# RF_test_board.net
KiCad netlist of a schematic drawn in EAGLE
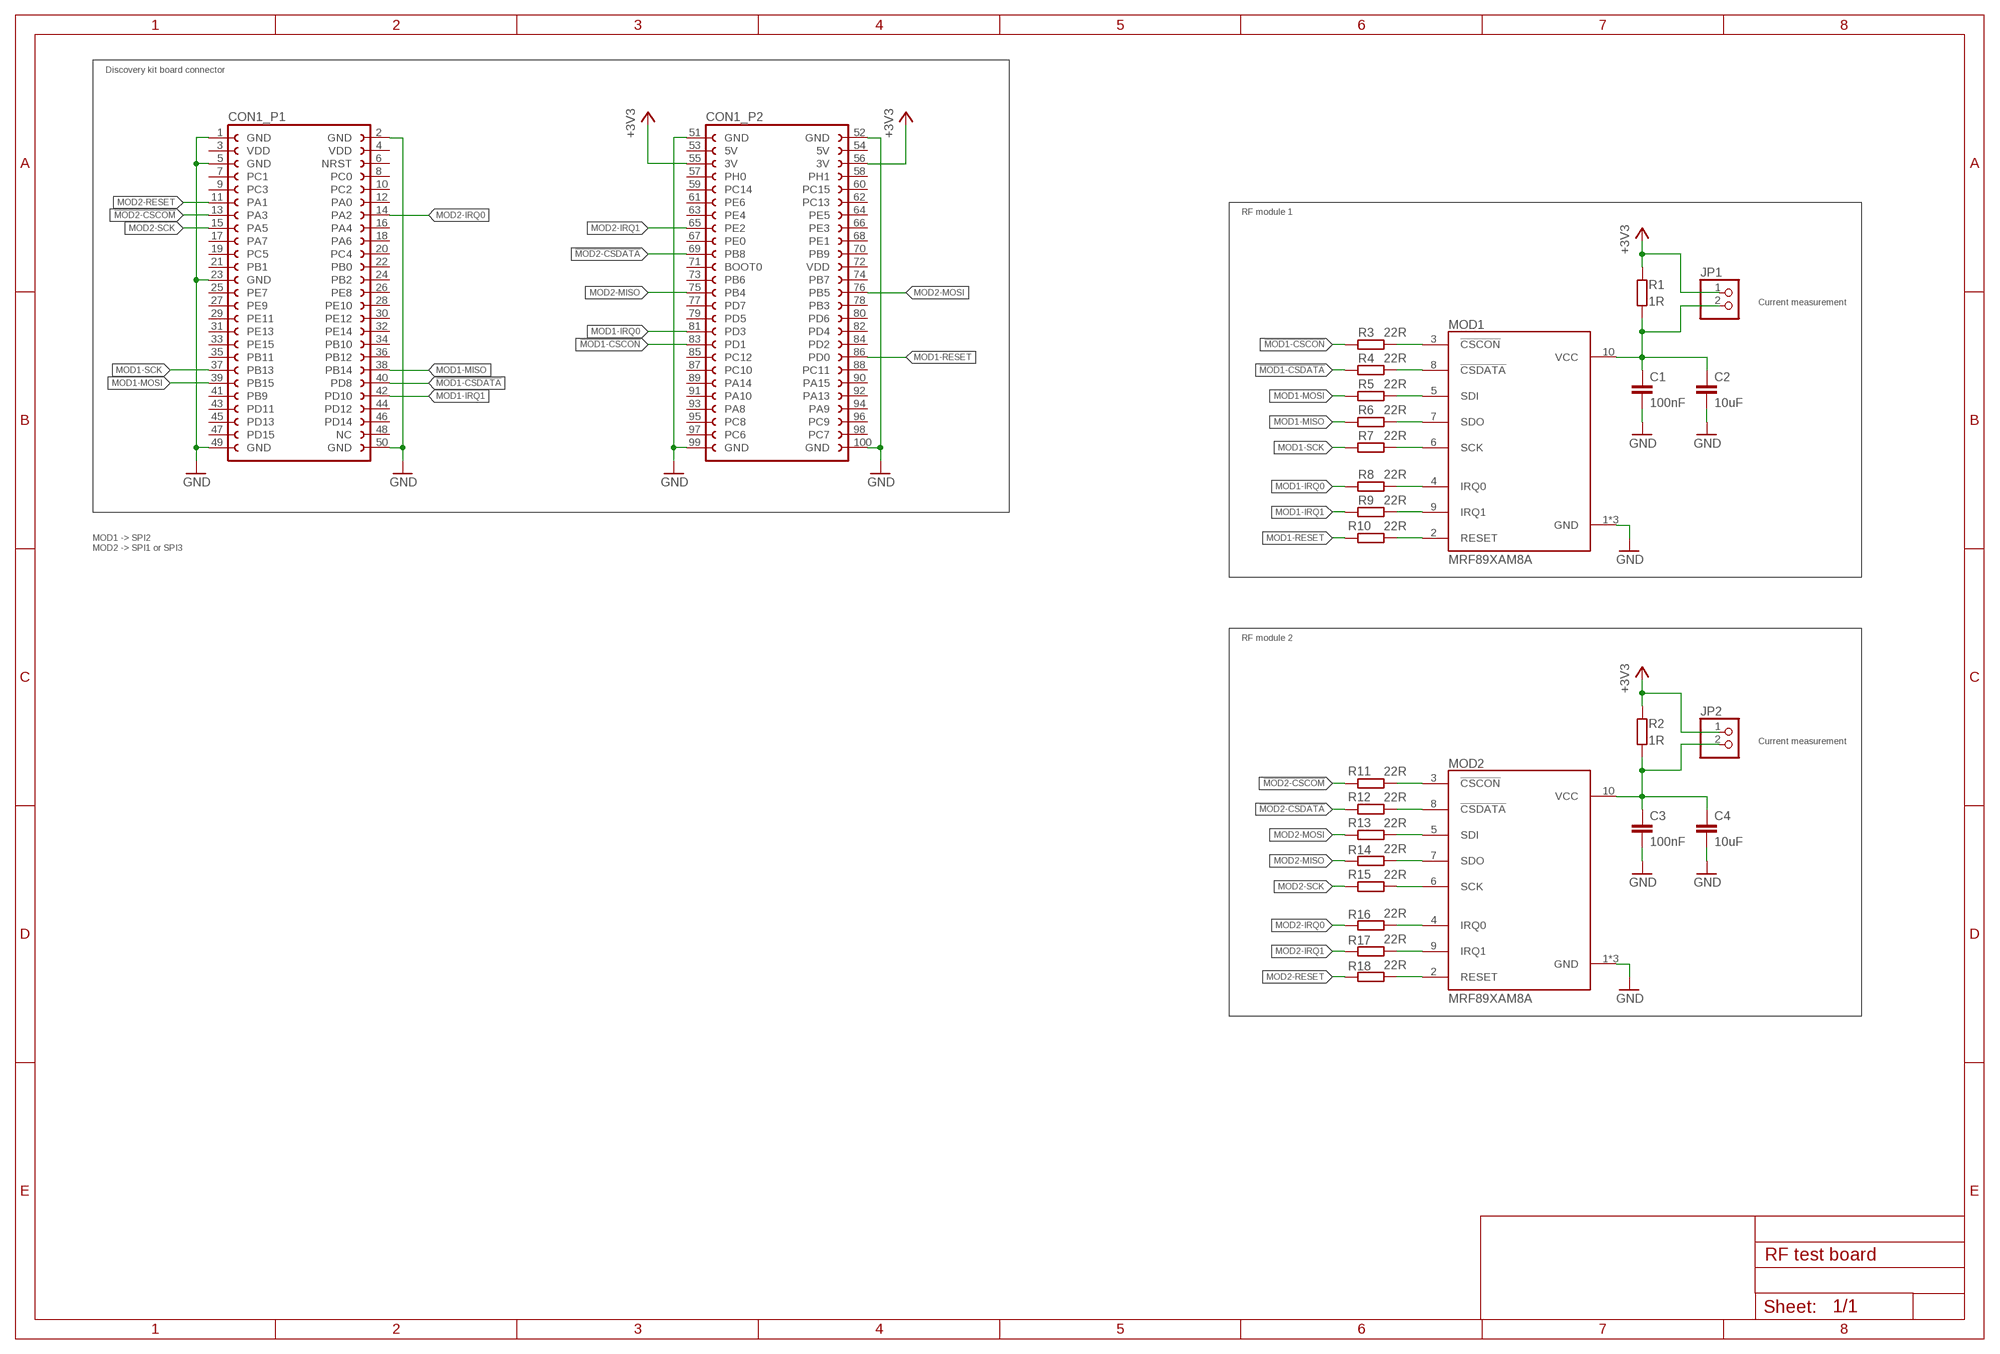
[diagram p0: schematic, sheet 1]

(export (version "E")
  (design (tool "Eeschema 10.0.6"))
  (components
    (comp (ref "C1")
      (value "100nF")
      (footprint "eagle-import:C0603K")
      (libsource (lib "eagle-import") (part "C-EUC0603K"))
    )
    (comp (ref "C2")
      (value "10uF")
      (footprint "eagle-import:C1206K")
      (libsource (lib "eagle-import") (part "C-EUC1206K"))
    )
    (comp (ref "C3")
      (value "100nF")
      (footprint "eagle-import:C0603K")
      (libsource (lib "eagle-import") (part "C-EUC0603K"))
    )
    (comp (ref "C4")
      (value "10uF")
      (footprint "eagle-import:C1206K")
      (libsource (lib "eagle-import") (part "C-EUC1206K"))
    )
    (comp (ref "CON1")
      (value "STM32F4DISCOVERY-CONNECTOR")
      (footprint "eagle-import:STM32F4DISCOVERY_CONNECTOR")
      (libsource (lib "eagle-import") (part "STM32F4DISCOVERY-CONNECTOR"))
    )
    (comp (ref "JP1")
      (value "PINHD-1X2")
      (footprint "eagle-import:1X02")
      (libsource (lib "eagle-import") (part "PINHD-1X2"))
    )
    (comp (ref "JP2")
      (value "PINHD-1X2")
      (footprint "eagle-import:1X02")
      (libsource (lib "eagle-import") (part "PINHD-1X2"))
    )
    (comp (ref "MOD1")
      (value "MRF89XAM8A")
      (footprint "eagle-import:MRF89XAM8A")
      (libsource (lib "eagle-import") (part "MRF89XAM8A"))
    )
    (comp (ref "MOD2")
      (value "MRF89XAM8A")
      (footprint "eagle-import:MRF89XAM8A")
      (libsource (lib "eagle-import") (part "MRF89XAM8A"))
    )
    (comp (ref "R1")
      (value "1R")
      (footprint "eagle-import:R0603")
      (libsource (lib "eagle-import") (part "R-EU_R0603"))
    )
    (comp (ref "R2")
      (value "1R")
      (footprint "eagle-import:R0603")
      (libsource (lib "eagle-import") (part "R-EU_R0603"))
    )
    (comp (ref "R3")
      (value "22R")
      (footprint "eagle-import:R0603")
      (libsource (lib "eagle-import") (part "R-EU_R0603"))
    )
    (comp (ref "R4")
      (value "22R")
      (footprint "eagle-import:R0603")
      (libsource (lib "eagle-import") (part "R-EU_R0603"))
    )
    (comp (ref "R5")
      (value "22R")
      (footprint "eagle-import:R0603")
      (libsource (lib "eagle-import") (part "R-EU_R0603"))
    )
    (comp (ref "R6")
      (value "22R")
      (footprint "eagle-import:R0603")
      (libsource (lib "eagle-import") (part "R-EU_R0603"))
    )
    (comp (ref "R7")
      (value "22R")
      (footprint "eagle-import:R0603")
      (libsource (lib "eagle-import") (part "R-EU_R0603"))
    )
    (comp (ref "R8")
      (value "22R")
      (footprint "eagle-import:R0603")
      (libsource (lib "eagle-import") (part "R-EU_R0603"))
    )
    (comp (ref "R9")
      (value "22R")
      (footprint "eagle-import:R0603")
      (libsource (lib "eagle-import") (part "R-EU_R0603"))
    )
    (comp (ref "R10")
      (value "22R")
      (footprint "eagle-import:R0603")
      (libsource (lib "eagle-import") (part "R-EU_R0603"))
    )
    (comp (ref "R11")
      (value "22R")
      (footprint "eagle-import:R0603")
      (libsource (lib "eagle-import") (part "R-EU_R0603"))
    )
    (comp (ref "R12")
      (value "22R")
      (footprint "eagle-import:R0603")
      (libsource (lib "eagle-import") (part "R-EU_R0603"))
    )
    (comp (ref "R13")
      (value "22R")
      (footprint "eagle-import:R0603")
      (libsource (lib "eagle-import") (part "R-EU_R0603"))
    )
    (comp (ref "R14")
      (value "22R")
      (footprint "eagle-import:R0603")
      (libsource (lib "eagle-import") (part "R-EU_R0603"))
    )
    (comp (ref "R15")
      (value "22R")
      (footprint "eagle-import:R0603")
      (libsource (lib "eagle-import") (part "R-EU_R0603"))
    )
    (comp (ref "R16")
      (value "22R")
      (footprint "eagle-import:R0603")
      (libsource (lib "eagle-import") (part "R-EU_R0603"))
    )
    (comp (ref "R17")
      (value "22R")
      (footprint "eagle-import:R0603")
      (libsource (lib "eagle-import") (part "R-EU_R0603"))
    )
    (comp (ref "R18")
      (value "22R")
      (footprint "eagle-import:R0603")
      (libsource (lib "eagle-import") (part "R-EU_R0603"))
    )
  )
  (nets
    (net (code "1") (name "+3V3") (class "Default")
      (node (ref "CON1") (pin "55") (pinfunction "3V_55") (pintype "passive"))
      (node (ref "CON1") (pin "56") (pinfunction "3V_56") (pintype "passive"))
      (node (ref "JP1") (pin "1") (pinfunction "1_1") (pintype "passive"))
      (node (ref "JP2") (pin "1") (pinfunction "1_1") (pintype "passive"))
      (node (ref "R1") (pin "2") (pinfunction "2_2") (pintype "passive"))
      (node (ref "R2") (pin "2") (pinfunction "2_2") (pintype "passive"))
    )
    (net (code "2") (name "/~{MOD1-CSCON}") (class "Default")
      (node (ref "CON1") (pin "83") (pinfunction "PD1_83") (pintype "passive"))
      (node (ref "R3") (pin "2") (pinfunction "2_2") (pintype "passive"))
    )
    (net (code "3") (name "/~{MOD1-CSDATA}") (class "Default")
      (node (ref "CON1") (pin "40") (pinfunction "PD8_40") (pintype "passive"))
      (node (ref "R4") (pin "2") (pinfunction "2_2") (pintype "passive"))
    )
    (net (code "4") (name "/~{MOD2-CSCOM}") (class "Default")
      (node (ref "CON1") (pin "13") (pinfunction "PA3_13") (pintype "passive"))
      (node (ref "R11") (pin "2") (pinfunction "2_2") (pintype "passive"))
    )
    (net (code "5") (name "/~{MOD2-CSDATA}") (class "Default")
      (node (ref "CON1") (pin "69") (pinfunction "PB8_69") (pintype "passive"))
      (node (ref "R12") (pin "2") (pinfunction "2_2") (pintype "passive"))
    )
    (net (code "6") (name "GND") (class "Default")
      (node (ref "C1") (pin "2") (pinfunction "2_2") (pintype "passive"))
      (node (ref "C2") (pin "2") (pinfunction "2_2") (pintype "passive"))
      (node (ref "C3") (pin "2") (pinfunction "2_2") (pintype "passive"))
      (node (ref "C4") (pin "2") (pinfunction "2_2") (pintype "passive"))
      (node (ref "CON1") (pin "1") (pinfunction "GND_1") (pintype "passive"))
      (node (ref "CON1") (pin "100") (pinfunction "GND_100") (pintype "passive"))
      (node (ref "CON1") (pin "2") (pinfunction "GND_2") (pintype "passive"))
      (node (ref "CON1") (pin "23") (pinfunction "GND_23") (pintype "passive"))
      (node (ref "CON1") (pin "49") (pinfunction "GND_49") (pintype "passive"))
      (node (ref "CON1") (pin "5") (pinfunction "GND_5") (pintype "passive"))
      (node (ref "CON1") (pin "50") (pinfunction "GND_50") (pintype "passive"))
      (node (ref "CON1") (pin "51") (pinfunction "GND_51") (pintype "passive"))
      (node (ref "CON1") (pin "52") (pinfunction "GND_52") (pintype "passive"))
      (node (ref "CON1") (pin "99") (pinfunction "GND_99") (pintype "passive"))
      (node (ref "MOD1") (pin "1") (pinfunction "GND_1") (pintype "bidirectional"))
      (node (ref "MOD1") (pin "11") (pinfunction "GND_11") (pintype "bidirectional"))
      (node (ref "MOD1") (pin "12") (pinfunction "GND_12") (pintype "bidirectional"))
      (node (ref "MOD2") (pin "1") (pinfunction "GND_1") (pintype "bidirectional"))
      (node (ref "MOD2") (pin "11") (pinfunction "GND_11") (pintype "bidirectional"))
      (node (ref "MOD2") (pin "12") (pinfunction "GND_12") (pintype "bidirectional"))
    )
    (net (code "7") (name "MOD1-IRQ0") (class "Default")
      (node (ref "CON1") (pin "81") (pinfunction "PD3_81") (pintype "passive"))
      (node (ref "R8") (pin "2") (pinfunction "2_2") (pintype "passive"))
    )
    (net (code "8") (name "MOD1-IRQ1") (class "Default")
      (node (ref "CON1") (pin "42") (pinfunction "PD10_42") (pintype "passive"))
      (node (ref "R9") (pin "2") (pinfunction "2_2") (pintype "passive"))
    )
    (net (code "9") (name "MOD1-MISO") (class "Default")
      (node (ref "CON1") (pin "38") (pinfunction "PB14_38") (pintype "passive"))
      (node (ref "R6") (pin "2") (pinfunction "2_2") (pintype "passive"))
    )
    (net (code "10") (name "MOD1-MOSI") (class "Default")
      (node (ref "CON1") (pin "39") (pinfunction "PB15_39") (pintype "passive"))
      (node (ref "R5") (pin "2") (pinfunction "2_2") (pintype "passive"))
    )
    (net (code "11") (name "MOD1-RESET") (class "Default")
      (node (ref "CON1") (pin "86") (pinfunction "PD0_86") (pintype "passive"))
      (node (ref "R10") (pin "2") (pinfunction "2_2") (pintype "passive"))
    )
    (net (code "12") (name "MOD1-SCK") (class "Default")
      (node (ref "CON1") (pin "37") (pinfunction "PB13_37") (pintype "passive"))
      (node (ref "R7") (pin "2") (pinfunction "2_2") (pintype "passive"))
    )
    (net (code "13") (name "MOD2-IRQ0") (class "Default")
      (node (ref "CON1") (pin "14") (pinfunction "PA2_14") (pintype "passive"))
      (node (ref "R16") (pin "2") (pinfunction "2_2") (pintype "passive"))
    )
    (net (code "14") (name "MOD2-IRQ1") (class "Default")
      (node (ref "CON1") (pin "65") (pinfunction "PE2_65") (pintype "passive"))
      (node (ref "R17") (pin "2") (pinfunction "2_2") (pintype "passive"))
    )
    (net (code "15") (name "MOD2-MISO") (class "Default")
      (node (ref "CON1") (pin "75") (pinfunction "PB4_75") (pintype "passive"))
      (node (ref "R14") (pin "2") (pinfunction "2_2") (pintype "passive"))
    )
    (net (code "16") (name "MOD2-MOSI") (class "Default")
      (node (ref "CON1") (pin "76") (pinfunction "PB5_76") (pintype "passive"))
      (node (ref "R13") (pin "2") (pinfunction "2_2") (pintype "passive"))
    )
    (net (code "17") (name "MOD2-RESET") (class "Default")
      (node (ref "CON1") (pin "11") (pinfunction "PA1_11") (pintype "passive"))
      (node (ref "R18") (pin "2") (pinfunction "2_2") (pintype "passive"))
    )
    (net (code "18") (name "MOD2-SCK") (class "Default")
      (node (ref "CON1") (pin "15") (pinfunction "PA5_15") (pintype "passive"))
      (node (ref "R15") (pin "2") (pinfunction "2_2") (pintype "passive"))
    )
    (net (code "19") (name "Net-(MOD1-IRQ0)") (class "Default")
      (node (ref "MOD1") (pin "4") (pinfunction "IRQ0_4") (pintype "bidirectional"))
      (node (ref "R8") (pin "1") (pinfunction "1_1") (pintype "passive"))
    )
    (net (code "20") (name "Net-(MOD1-IRQ1)") (class "Default")
      (node (ref "MOD1") (pin "9") (pinfunction "IRQ1_9") (pintype "bidirectional"))
      (node (ref "R9") (pin "1") (pinfunction "1_1") (pintype "passive"))
    )
    (net (code "21") (name "Net-(MOD1-RESET)") (class "Default")
      (node (ref "MOD1") (pin "2") (pinfunction "RESET_2") (pintype "bidirectional"))
      (node (ref "R10") (pin "1") (pinfunction "1_1") (pintype "passive"))
    )
    (net (code "22") (name "Net-(MOD1-SCK)") (class "Default")
      (node (ref "MOD1") (pin "6") (pinfunction "SCK_6") (pintype "bidirectional"))
      (node (ref "R7") (pin "1") (pinfunction "1_1") (pintype "passive"))
    )
    (net (code "23") (name "Net-(MOD1-SDI)") (class "Default")
      (node (ref "MOD1") (pin "5") (pinfunction "SDI_5") (pintype "bidirectional"))
      (node (ref "R5") (pin "1") (pinfunction "1_1") (pintype "passive"))
    )
    (net (code "24") (name "Net-(MOD1-SDO)") (class "Default")
      (node (ref "MOD1") (pin "7") (pinfunction "SDO_7") (pintype "bidirectional"))
      (node (ref "R6") (pin "1") (pinfunction "1_1") (pintype "passive"))
    )
    (net (code "25") (name "Net-(MOD1-VCC)") (class "Default")
      (node (ref "C1") (pin "1") (pinfunction "1_1") (pintype "passive"))
      (node (ref "C2") (pin "1") (pinfunction "1_1") (pintype "passive"))
      (node (ref "JP1") (pin "2") (pinfunction "2_2") (pintype "passive"))
      (node (ref "MOD1") (pin "10") (pinfunction "VCC_10") (pintype "bidirectional"))
      (node (ref "R1") (pin "1") (pinfunction "1_1") (pintype "passive"))
    )
    (net (code "26") (name "Net-(MOD1-~{CSCON})") (class "Default")
      (node (ref "MOD1") (pin "3") (pinfunction "~{CSCON}_3") (pintype "bidirectional"))
      (node (ref "R3") (pin "1") (pinfunction "1_1") (pintype "passive"))
    )
    (net (code "27") (name "Net-(MOD1-~{CSDATA})") (class "Default")
      (node (ref "MOD1") (pin "8") (pinfunction "~{CSDATA}_8") (pintype "bidirectional"))
      (node (ref "R4") (pin "1") (pinfunction "1_1") (pintype "passive"))
    )
    (net (code "28") (name "Net-(MOD2-IRQ0)") (class "Default")
      (node (ref "MOD2") (pin "4") (pinfunction "IRQ0_4") (pintype "bidirectional"))
      (node (ref "R16") (pin "1") (pinfunction "1_1") (pintype "passive"))
    )
    (net (code "29") (name "Net-(MOD2-IRQ1)") (class "Default")
      (node (ref "MOD2") (pin "9") (pinfunction "IRQ1_9") (pintype "bidirectional"))
      (node (ref "R17") (pin "1") (pinfunction "1_1") (pintype "passive"))
    )
    (net (code "30") (name "Net-(MOD2-RESET)") (class "Default")
      (node (ref "MOD2") (pin "2") (pinfunction "RESET_2") (pintype "bidirectional"))
      (node (ref "R18") (pin "1") (pinfunction "1_1") (pintype "passive"))
    )
    (net (code "31") (name "Net-(MOD2-SCK)") (class "Default")
      (node (ref "MOD2") (pin "6") (pinfunction "SCK_6") (pintype "bidirectional"))
      (node (ref "R15") (pin "1") (pinfunction "1_1") (pintype "passive"))
    )
    (net (code "32") (name "Net-(MOD2-SDI)") (class "Default")
      (node (ref "MOD2") (pin "5") (pinfunction "SDI_5") (pintype "bidirectional"))
      (node (ref "R13") (pin "1") (pinfunction "1_1") (pintype "passive"))
    )
    (net (code "33") (name "Net-(MOD2-SDO)") (class "Default")
      (node (ref "MOD2") (pin "7") (pinfunction "SDO_7") (pintype "bidirectional"))
      (node (ref "R14") (pin "1") (pinfunction "1_1") (pintype "passive"))
    )
    (net (code "34") (name "Net-(MOD2-VCC)") (class "Default")
      (node (ref "C3") (pin "1") (pinfunction "1_1") (pintype "passive"))
      (node (ref "C4") (pin "1") (pinfunction "1_1") (pintype "passive"))
      (node (ref "JP2") (pin "2") (pinfunction "2_2") (pintype "passive"))
      (node (ref "MOD2") (pin "10") (pinfunction "VCC_10") (pintype "bidirectional"))
      (node (ref "R2") (pin "1") (pinfunction "1_1") (pintype "passive"))
    )
    (net (code "35") (name "Net-(MOD2-~{CSCON})") (class "Default")
      (node (ref "MOD2") (pin "3") (pinfunction "~{CSCON}_3") (pintype "bidirectional"))
      (node (ref "R11") (pin "1") (pinfunction "1_1") (pintype "passive"))
    )
    (net (code "36") (name "Net-(MOD2-~{CSDATA})") (class "Default")
      (node (ref "MOD2") (pin "8") (pinfunction "~{CSDATA}_8") (pintype "bidirectional"))
      (node (ref "R12") (pin "1") (pinfunction "1_1") (pintype "passive"))
    )
    (net (code "37") (name "unconnected-(CON1A-NC-Pad48)") (class "Default")
      (node (ref "CON1") (pin "48") (pinfunction "NC_48") (pintype "passive"))
    )
    (net (code "38") (name "unconnected-(CON1A-NRST-Pad6)") (class "Default")
      (node (ref "CON1") (pin "6") (pinfunction "NRST_6") (pintype "passive"))
    )
    (net (code "39") (name "unconnected-(CON1A-PA0-Pad12)") (class "Default")
      (node (ref "CON1") (pin "12") (pinfunction "PA0_12") (pintype "passive"))
    )
    (net (code "40") (name "unconnected-(CON1A-PA4-Pad16)") (class "Default")
      (node (ref "CON1") (pin "16") (pinfunction "PA4_16") (pintype "passive"))
    )
    (net (code "41") (name "unconnected-(CON1A-PA6-Pad18)") (class "Default")
      (node (ref "CON1") (pin "18") (pinfunction "PA6_18") (pintype "passive"))
    )
    (net (code "42") (name "unconnected-(CON1A-PA7-Pad17)") (class "Default")
      (node (ref "CON1") (pin "17") (pinfunction "PA7_17") (pintype "passive"))
    )
    (net (code "43") (name "unconnected-(CON1A-PB0-Pad22)") (class "Default")
      (node (ref "CON1") (pin "22") (pinfunction "PB0_22") (pintype "passive"))
    )
    (net (code "44") (name "unconnected-(CON1A-PB1-Pad21)") (class "Default")
      (node (ref "CON1") (pin "21") (pinfunction "PB1_21") (pintype "passive"))
    )
    (net (code "45") (name "unconnected-(CON1A-PB2-Pad24)") (class "Default")
      (node (ref "CON1") (pin "24") (pinfunction "PB2_24") (pintype "passive"))
    )
    (net (code "46") (name "unconnected-(CON1A-PB9-Pad41)") (class "Default")
      (node (ref "CON1") (pin "41") (pinfunction "PB9_41") (pintype "passive"))
    )
    (net (code "47") (name "unconnected-(CON1A-PB10-Pad34)") (class "Default")
      (node (ref "CON1") (pin "34") (pinfunction "PB10_34") (pintype "passive"))
    )
    (net (code "48") (name "unconnected-(CON1A-PB11-Pad35)") (class "Default")
      (node (ref "CON1") (pin "35") (pinfunction "PB11_35") (pintype "passive"))
    )
    (net (code "49") (name "unconnected-(CON1A-PB12-Pad36)") (class "Default")
      (node (ref "CON1") (pin "36") (pinfunction "PB12_36") (pintype "passive"))
    )
    (net (code "50") (name "unconnected-(CON1A-PC0-Pad8)") (class "Default")
      (node (ref "CON1") (pin "8") (pinfunction "PC0_8") (pintype "passive"))
    )
    (net (code "51") (name "unconnected-(CON1A-PC1-Pad7)") (class "Default")
      (node (ref "CON1") (pin "7") (pinfunction "PC1_7") (pintype "passive"))
    )
    (net (code "52") (name "unconnected-(CON1A-PC2-Pad10)") (class "Default")
      (node (ref "CON1") (pin "10") (pinfunction "PC2_10") (pintype "passive"))
    )
    (net (code "53") (name "unconnected-(CON1A-PC3-Pad9)") (class "Default")
      (node (ref "CON1") (pin "9") (pinfunction "PC3_9") (pintype "passive"))
    )
    (net (code "54") (name "unconnected-(CON1A-PC4-Pad20)") (class "Default")
      (node (ref "CON1") (pin "20") (pinfunction "PC4_20") (pintype "passive"))
    )
    (net (code "55") (name "unconnected-(CON1A-PC5-Pad19)") (class "Default")
      (node (ref "CON1") (pin "19") (pinfunction "PC5_19") (pintype "passive"))
    )
    (net (code "56") (name "unconnected-(CON1A-PD11-Pad43)") (class "Default")
      (node (ref "CON1") (pin "43") (pinfunction "PD11_43") (pintype "passive"))
    )
    (net (code "57") (name "unconnected-(CON1A-PD12-Pad44)") (class "Default")
      (node (ref "CON1") (pin "44") (pinfunction "PD12_44") (pintype "passive"))
    )
    (net (code "58") (name "unconnected-(CON1A-PD13-Pad45)") (class "Default")
      (node (ref "CON1") (pin "45") (pinfunction "PD13_45") (pintype "passive"))
    )
    (net (code "59") (name "unconnected-(CON1A-PD14-Pad46)") (class "Default")
      (node (ref "CON1") (pin "46") (pinfunction "PD14_46") (pintype "passive"))
    )
    (net (code "60") (name "unconnected-(CON1A-PD15-Pad47)") (class "Default")
      (node (ref "CON1") (pin "47") (pinfunction "PD15_47") (pintype "passive"))
    )
    (net (code "61") (name "unconnected-(CON1A-PE7-Pad25)") (class "Default")
      (node (ref "CON1") (pin "25") (pinfunction "PE7_25") (pintype "passive"))
    )
    (net (code "62") (name "unconnected-(CON1A-PE8-Pad26)") (class "Default")
      (node (ref "CON1") (pin "26") (pinfunction "PE8_26") (pintype "passive"))
    )
    (net (code "63") (name "unconnected-(CON1A-PE9-Pad27)") (class "Default")
      (node (ref "CON1") (pin "27") (pinfunction "PE9_27") (pintype "passive"))
    )
    (net (code "64") (name "unconnected-(CON1A-PE10-Pad28)") (class "Default")
      (node (ref "CON1") (pin "28") (pinfunction "PE10_28") (pintype "passive"))
    )
    (net (code "65") (name "unconnected-(CON1A-PE11-Pad29)") (class "Default")
      (node (ref "CON1") (pin "29") (pinfunction "PE11_29") (pintype "passive"))
    )
    (net (code "66") (name "unconnected-(CON1A-PE12-Pad30)") (class "Default")
      (node (ref "CON1") (pin "30") (pinfunction "PE12_30") (pintype "passive"))
    )
    (net (code "67") (name "unconnected-(CON1A-PE13-Pad31)") (class "Default")
      (node (ref "CON1") (pin "31") (pinfunction "PE13_31") (pintype "passive"))
    )
    (net (code "68") (name "unconnected-(CON1A-PE14-Pad32)") (class "Default")
      (node (ref "CON1") (pin "32") (pinfunction "PE14_32") (pintype "passive"))
    )
    (net (code "69") (name "unconnected-(CON1A-PE15-Pad33)") (class "Default")
      (node (ref "CON1") (pin "33") (pinfunction "PE15_33") (pintype "passive"))
    )
    (net (code "70") (name "unconnected-(CON1A-VDD-Pad3)") (class "Default")
      (node (ref "CON1") (pin "3") (pinfunction "VDD_3") (pintype "passive"))
    )
    (net (code "71") (name "unconnected-(CON1A-VDD-Pad4)") (class "Default")
      (node (ref "CON1") (pin "4") (pinfunction "VDD_4") (pintype "passive"))
    )
    (net (code "72") (name "unconnected-(CON1B-5V-Pad53)") (class "Default")
      (node (ref "CON1") (pin "53") (pinfunction "5V_53") (pintype "passive"))
    )
    (net (code "73") (name "unconnected-(CON1B-5V-Pad54)") (class "Default")
      (node (ref "CON1") (pin "54") (pinfunction "5V_54") (pintype "passive"))
    )
    (net (code "74") (name "unconnected-(CON1B-BOOT0-Pad71)") (class "Default")
      (node (ref "CON1") (pin "71") (pinfunction "BOOT0_71") (pintype "passive"))
    )
    (net (code "75") (name "unconnected-(CON1B-PA8-Pad93)") (class "Default")
      (node (ref "CON1") (pin "93") (pinfunction "PA8_93") (pintype "passive"))
    )
    (net (code "76") (name "unconnected-(CON1B-PA9-Pad94)") (class "Default")
      (node (ref "CON1") (pin "94") (pinfunction "PA9_94") (pintype "passive"))
    )
    (net (code "77") (name "unconnected-(CON1B-PA10-Pad91)") (class "Default")
      (node (ref "CON1") (pin "91") (pinfunction "PA10_91") (pintype "passive"))
    )
    (net (code "78") (name "unconnected-(CON1B-PA13-Pad92)") (class "Default")
      (node (ref "CON1") (pin "92") (pinfunction "PA13_92") (pintype "passive"))
    )
    (net (code "79") (name "unconnected-(CON1B-PA14-Pad89)") (class "Default")
      (node (ref "CON1") (pin "89") (pinfunction "PA14_89") (pintype "passive"))
    )
    (net (code "80") (name "unconnected-(CON1B-PA15-Pad90)") (class "Default")
      (node (ref "CON1") (pin "90") (pinfunction "PA15_90") (pintype "passive"))
    )
    (net (code "81") (name "unconnected-(CON1B-PB3-Pad78)") (class "Default")
      (node (ref "CON1") (pin "78") (pinfunction "PB3_78") (pintype "passive"))
    )
    (net (code "82") (name "unconnected-(CON1B-PB6-Pad73)") (class "Default")
      (node (ref "CON1") (pin "73") (pinfunction "PB6_73") (pintype "passive"))
    )
    (net (code "83") (name "unconnected-(CON1B-PB7-Pad74)") (class "Default")
      (node (ref "CON1") (pin "74") (pinfunction "PB7_74") (pintype "passive"))
    )
    (net (code "84") (name "unconnected-(CON1B-PB9-Pad70)") (class "Default")
      (node (ref "CON1") (pin "70") (pinfunction "PB9_70") (pintype "passive"))
    )
    (net (code "85") (name "unconnected-(CON1B-PC6-Pad97)") (class "Default")
      (node (ref "CON1") (pin "97") (pinfunction "PC6_97") (pintype "passive"))
    )
    (net (code "86") (name "unconnected-(CON1B-PC7-Pad98)") (class "Default")
      (node (ref "CON1") (pin "98") (pinfunction "PC7_98") (pintype "passive"))
    )
    (net (code "87") (name "unconnected-(CON1B-PC8-Pad95)") (class "Default")
      (node (ref "CON1") (pin "95") (pinfunction "PC8_95") (pintype "passive"))
    )
    (net (code "88") (name "unconnected-(CON1B-PC9-Pad96)") (class "Default")
      (node (ref "CON1") (pin "96") (pinfunction "PC9_96") (pintype "passive"))
    )
    (net (code "89") (name "unconnected-(CON1B-PC10-Pad87)") (class "Default")
      (node (ref "CON1") (pin "87") (pinfunction "PC10_87") (pintype "passive"))
    )
    (net (code "90") (name "unconnected-(CON1B-PC11-Pad88)") (class "Default")
      (node (ref "CON1") (pin "88") (pinfunction "PC11_88") (pintype "passive"))
    )
    (net (code "91") (name "unconnected-(CON1B-PC12-Pad85)") (class "Default")
      (node (ref "CON1") (pin "85") (pinfunction "PC12_85") (pintype "passive"))
    )
    (net (code "92") (name "unconnected-(CON1B-PC13-Pad62)") (class "Default")
      (node (ref "CON1") (pin "62") (pinfunction "PC13_62") (pintype "passive"))
    )
    (net (code "93") (name "unconnected-(CON1B-PC14-Pad59)") (class "Default")
      (node (ref "CON1") (pin "59") (pinfunction "PC14_59") (pintype "passive"))
    )
    (net (code "94") (name "unconnected-(CON1B-PC15-Pad60)") (class "Default")
      (node (ref "CON1") (pin "60") (pinfunction "PC15_60") (pintype "passive"))
    )
    (net (code "95") (name "unconnected-(CON1B-PD2-Pad84)") (class "Default")
      (node (ref "CON1") (pin "84") (pinfunction "PD2_84") (pintype "passive"))
    )
    (net (code "96") (name "unconnected-(CON1B-PD4-Pad82)") (class "Default")
      (node (ref "CON1") (pin "82") (pinfunction "PD4_82") (pintype "passive"))
    )
    (net (code "97") (name "unconnected-(CON1B-PD5-Pad79)") (class "Default")
      (node (ref "CON1") (pin "79") (pinfunction "PD5_79") (pintype "passive"))
    )
    (net (code "98") (name "unconnected-(CON1B-PD6-Pad80)") (class "Default")
      (node (ref "CON1") (pin "80") (pinfunction "PD6_80") (pintype "passive"))
    )
    (net (code "99") (name "unconnected-(CON1B-PD7-Pad77)") (class "Default")
      (node (ref "CON1") (pin "77") (pinfunction "PD7_77") (pintype "passive"))
    )
    (net (code "100") (name "unconnected-(CON1B-PE0-Pad67)") (class "Default")
      (node (ref "CON1") (pin "67") (pinfunction "PE0_67") (pintype "passive"))
    )
    (net (code "101") (name "unconnected-(CON1B-PE1-Pad68)") (class "Default")
      (node (ref "CON1") (pin "68") (pinfunction "PE1_68") (pintype "passive"))
    )
    (net (code "102") (name "unconnected-(CON1B-PE3-Pad66)") (class "Default")
      (node (ref "CON1") (pin "66") (pinfunction "PE3_66") (pintype "passive"))
    )
    (net (code "103") (name "unconnected-(CON1B-PE4-Pad63)") (class "Default")
      (node (ref "CON1") (pin "63") (pinfunction "PE4_63") (pintype "passive"))
    )
    (net (code "104") (name "unconnected-(CON1B-PE5-Pad64)") (class "Default")
      (node (ref "CON1") (pin "64") (pinfunction "PE5_64") (pintype "passive"))
    )
    (net (code "105") (name "unconnected-(CON1B-PE6-Pad61)") (class "Default")
      (node (ref "CON1") (pin "61") (pinfunction "PE6_61") (pintype "passive"))
    )
    (net (code "106") (name "unconnected-(CON1B-PH0-Pad57)") (class "Default")
      (node (ref "CON1") (pin "57") (pinfunction "PH0_57") (pintype "passive"))
    )
    (net (code "107") (name "unconnected-(CON1B-PH1-Pad58)") (class "Default")
      (node (ref "CON1") (pin "58") (pinfunction "PH1_58") (pintype "passive"))
    )
    (net (code "108") (name "unconnected-(CON1B-VDD-Pad72)") (class "Default")
      (node (ref "CON1") (pin "72") (pinfunction "VDD_72") (pintype "passive"))
    )
  )
)
